# FEEL_2021_MCU.net
KiCad netlist of a schematic drawn in Altium Designer
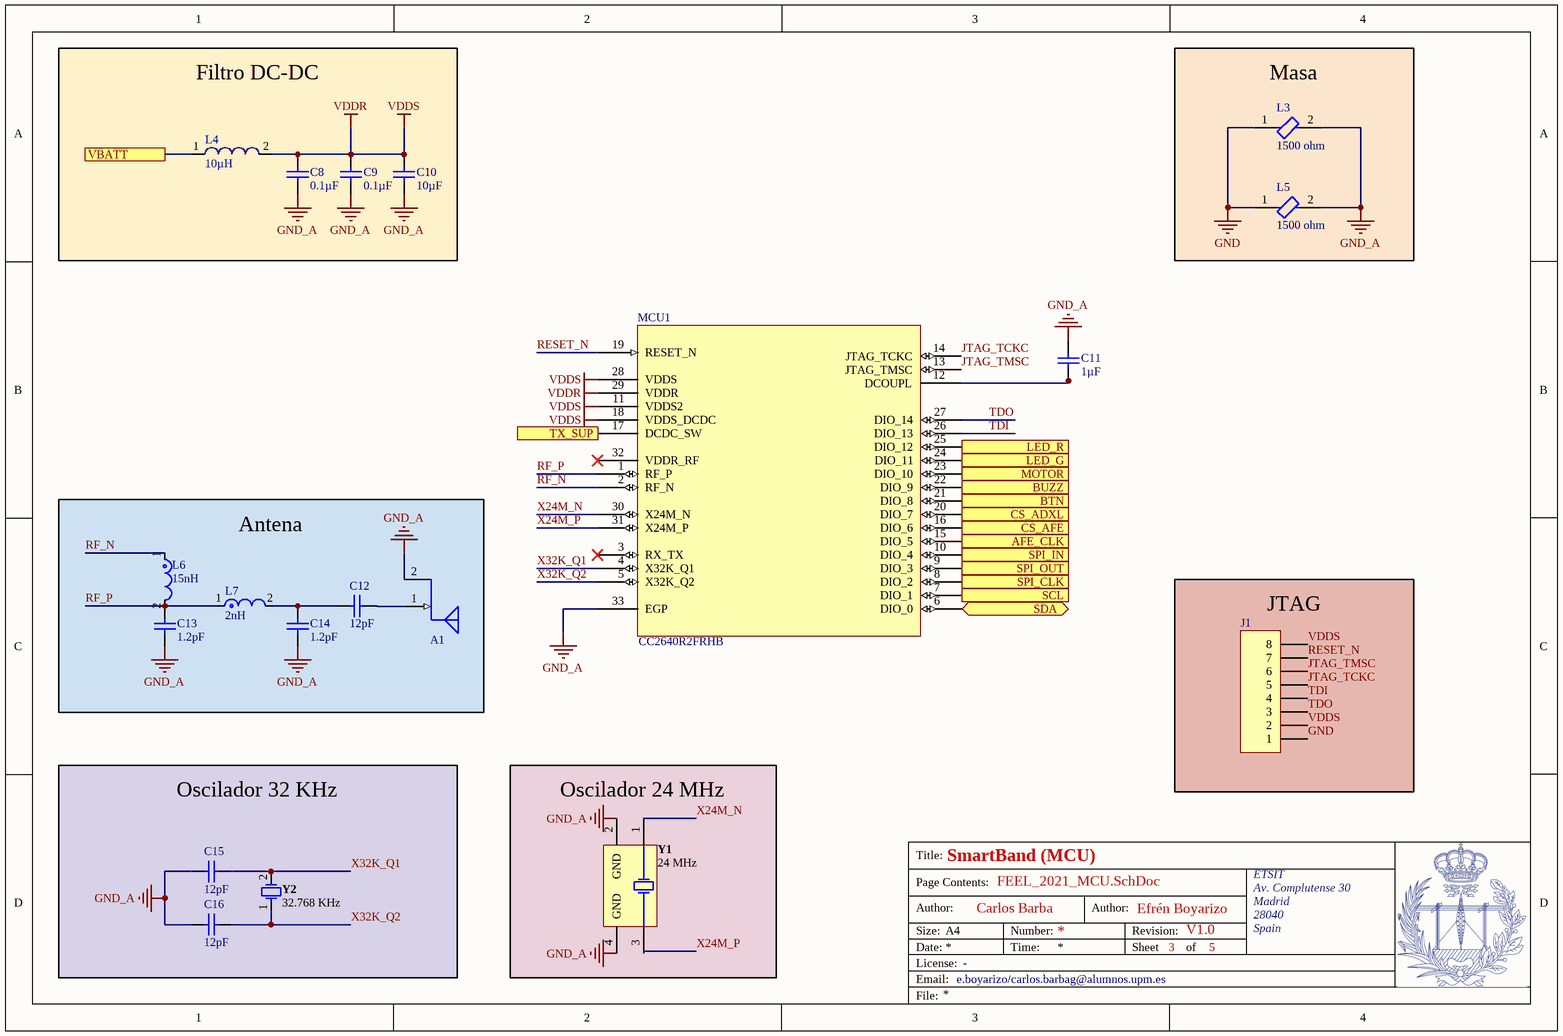
[diagram p0: FEEL_2021_MCU.SchDoc]

(export (version "E")
  (design (tool "Eeschema 10.0.6"))
  (components
    (comp (ref "A1") (value "-") (footprint "PCBAntenna") (libsource (lib "FEEL2122") (part "PCBAntenna")))
    (comp (ref "C8")
      (value "0.1µF")
      (footprint "CAPC1608X90X35ML10T15")
      (description "Chip Capacitor, 22 pF, +/- 5%, 50 V, -55 to 125 degC, 0603 (1608 Metric), RoHS, Tape and Reel")
      (fields (field (name "MANUFACTURER") "Murata"))
      (libsource (lib "Altium Content Vault") (part "CAP-NP-2"))
    )
    (comp (ref "C9")
      (value "0.1µF")
      (footprint "CAPC1608X90X35ML10T15")
      (description "Chip Capacitor, 22 pF, +/- 5%, 50 V, -55 to 125 degC, 0603 (1608 Metric), RoHS, Tape and Reel")
      (fields (field (name "MANUFACTURER") "Murata"))
      (libsource (lib "Altium Content Vault") (part "CAP-NP-2"))
    )
    (comp (ref "C10")
      (value "10µF")
      (footprint "CAPC1608X90X35ML10T15")
      (description "Chip Capacitor, 22 pF, +/- 5%, 50 V, -55 to 125 degC, 0603 (1608 Metric), RoHS, Tape and Reel")
      (fields (field (name "MANUFACTURER") "Murata"))
      (libsource (lib "Altium Content Vault") (part "CAP-NP-2"))
    )
    (comp (ref "C11")
      (value "1µF")
      (footprint "CAPC1608X90X35ML10T15")
      (description "Chip Capacitor, 22 pF, +/- 5%, 50 V, -55 to 125 degC, 0603 (1608 Metric), RoHS, Tape and Reel")
      (fields (field (name "MANUFACTURER") "Murata"))
      (libsource (lib "Altium Content Vault") (part "CAP-NP-2"))
    )
    (comp (ref "C12")
      (value "12pF")
      (footprint "CAPC1608X90X35ML10T15")
      (description "Chip Capacitor, 22 pF, +/- 5%, 50 V, -55 to 125 degC, 0603 (1608 Metric), RoHS, Tape and Reel")
      (fields (field (name "MANUFACTURER") "Murata"))
      (libsource (lib "Altium Content Vault") (part "CAP-NP-2"))
    )
    (comp (ref "C13")
      (value "1.2pF")
      (footprint "CAPC1608X90X35ML10T15")
      (description "Chip Capacitor, 22 pF, +/- 5%, 50 V, -55 to 125 degC, 0603 (1608 Metric), RoHS, Tape and Reel")
      (fields (field (name "MANUFACTURER") "Murata"))
      (libsource (lib "Altium Content Vault") (part "CAP-NP-2"))
    )
    (comp (ref "C14")
      (value "1.2pF")
      (footprint "CAPC1608X90X35ML10T15")
      (description "Chip Capacitor, 22 pF, +/- 5%, 50 V, -55 to 125 degC, 0603 (1608 Metric), RoHS, Tape and Reel")
      (fields (field (name "MANUFACTURER") "Murata"))
      (libsource (lib "Altium Content Vault") (part "CAP-NP-2"))
    )
    (comp (ref "C15")
      (value "12pF")
      (footprint "CAPC1608X90X35ML10T15")
      (description "Chip Capacitor, 22 pF, +/- 5%, 50 V, -55 to 125 degC, 0603 (1608 Metric), RoHS, Tape and Reel")
      (fields (field (name "MANUFACTURER") "Murata"))
      (libsource (lib "Altium Content Vault") (part "CAP-NP-2"))
    )
    (comp (ref "C16")
      (value "12pF")
      (footprint "CAPC1608X90X35ML10T15")
      (description "Chip Capacitor, 22 pF, +/- 5%, 50 V, -55 to 125 degC, 0603 (1608 Metric), RoHS, Tape and Reel")
      (fields (field (name "MANUFACTURER") "Murata"))
      (libsource (lib "Altium Content Vault") (part "CAP-NP-2"))
    )
    (comp (ref "J1")
      (value "~")
      (footprint "HDR1X8")
      (description "Header, 8-Pin")
      (fields (field (name "PUBLISHER") "Altium Limited"))
      (libsource (lib "Miscellaneous Connectors") (part "Header 8"))
    )
    (comp (ref "L3")
      (value "1500 ohm")
      (footprint "FP-BLM18-0_15-t0_8-MFG")
      (description "Chip Ferrite Bead, 0603, 600Ω @ 100MHz, 0.35Ω, 25%, 500mA")
      (fields (field (name "TOLERANCE") "25%"))
      (libsource (lib "Altium Content Vault") (part "5f30dd21d616792df468990f7003faa"))
    )
    (comp (ref "L4")
      (value "10µH")
      (footprint "SMD 2510")
      (description "Power Multilayer Inductor WE-MAPI, L=10.0µH")
      (fields (field (name "PARTNUMBER") "74438323100") (field (name "MANUFACTURER") "Wuerth Elektronik"))
      (libsource (lib "Altium Content Vault") (part "WE-IND-INDUCTOR-2"))
    )
    (comp (ref "L5")
      (value "1500 ohm")
      (footprint "FP-BLM18-0_15-t0_8-MFG")
      (description "Chip Ferrite Bead, 0603, 600Ω @ 100MHz, 0.35Ω, 25%, 500mA")
      (fields (field (name "TOLERANCE") "25%"))
      (libsource (lib "Altium Content Vault") (part "5f30dd21d616792df468990f7003faa"))
    )
    (comp (ref "L6")
      (value "15nH")
      (footprint "FP-LQG15HH_02-IPC_B")
      (description "Multilayer type RF Inductor 2.4nH ±0.3nH 0.1Ω 800mA 0402")
      (fields (field (name "TOLERANCE") "5%"))
      (libsource (lib "Altium Content Vault") (part "4cc4b267dca4c8e51f7102f422741d8"))
    )
    (comp (ref "L7")
      (value "2nH")
      (footprint "FP-LQG15HH_02-IPC_B")
      (description "Multilayer type RF Inductor 2.4nH ±0.3nH 0.1Ω 800mA 0402")
      (fields (field (name "TOLERANCE") "5%"))
      (libsource (lib "Altium Content Vault") (part "4cc4b267dca4c8e51f7102f422741d8"))
    )
    (comp (ref "MCU1")
      (value "~")
      (footprint "DEOP2021-Calle-Payno")
      (libsource (lib "FEEL2122") (part "CC2640R2FRHB"))
    )
    (comp (ref "Y1")
      (value "24 MHz")
      (footprint "ABRA-ABM3B-4_V")
      (description "Ceramic SMD Crystal, 24 MHz, +/- 20 ppm, 50 Ohm, -20 to 70 degC, 4-Pin SMD, RoHS, Tape and Reel")
      (libsource (lib "Altium Content Vault") (part "XTAL-1-3-4"))
    )
    (comp (ref "Y2")
      (value "32.768 KHz")
      (footprint "ABRA-ABS07_A_V")
      (description "Tuning Fork Crystal, 32.768 KHz, +/- 20 ppm, -40 to 85 degC, 2-Pin SMD, RoHS, Tape and Reel")
      (fields (field (name "MANUFACTURER") "Abracon") (field (name "TOLERANCE") "20ppm"))
      (libsource (lib "Altium Content Vault") (part "XTAL-1-2-2"))
    )
  )
  (nets
    (net (code "1") (name "/AFE_CLK") (class "Default")
      (node (ref "MCU1") (pin "15") (pinfunction "DIO_5_15") (pintype "bidirectional"))
    )
    (net (code "2") (name "/BTN") (class "Default")
      (node (ref "MCU1") (pin "21") (pinfunction "DIO_8_21") (pintype "bidirectional"))
    )
    (net (code "3") (name "/BUZZ") (class "Default")
      (node (ref "MCU1") (pin "22") (pinfunction "DIO_9_22") (pintype "bidirectional"))
    )
    (net (code "4") (name "/CS_ADXL") (class "Default")
      (node (ref "MCU1") (pin "20") (pinfunction "DIO_7_20") (pintype "bidirectional"))
    )
    (net (code "5") (name "/CS_AFE") (class "Default")
      (node (ref "MCU1") (pin "16") (pinfunction "DIO_6_16") (pintype "bidirectional"))
    )
    (net (code "6") (name "/JTAG_TCKC") (class "Default")
      (node (ref "J1") (pin "5") (pinfunction "5_5") (pintype "passive"))
      (node (ref "MCU1") (pin "14") (pinfunction "JTAG_TCKC_14") (pintype "bidirectional"))
    )
    (net (code "7") (name "/JTAG_TMSC") (class "Default")
      (node (ref "J1") (pin "6") (pinfunction "6_6") (pintype "passive"))
      (node (ref "MCU1") (pin "13") (pinfunction "JTAG_TMSC_13") (pintype "bidirectional"))
    )
    (net (code "8") (name "/LED_G") (class "Default")
      (node (ref "MCU1") (pin "24") (pinfunction "DIO_11_24") (pintype "bidirectional"))
    )
    (net (code "9") (name "/LED_R") (class "Default")
      (node (ref "MCU1") (pin "25") (pinfunction "DIO_12_25") (pintype "bidirectional"))
    )
    (net (code "10") (name "/MOTOR") (class "Default")
      (node (ref "MCU1") (pin "23") (pinfunction "DIO_10_23") (pintype "bidirectional"))
    )
    (net (code "11") (name "/RESET_N") (class "Default")
      (node (ref "J1") (pin "7") (pinfunction "7_7") (pintype "passive"))
      (node (ref "MCU1") (pin "19") (pinfunction "RESET_N_19") (pintype "input"))
    )
    (net (code "12") (name "/RF_N") (class "Default")
      (node (ref "L6") (pin "1") (pinfunction "1_1") (pintype "passive"))
      (node (ref "MCU1") (pin "2") (pinfunction "RF_N_2") (pintype "bidirectional"))
    )
    (net (code "13") (name "/RF_P") (class "Default")
      (node (ref "C13") (pin "2") (pinfunction "2_2") (pintype "passive"))
      (node (ref "L6") (pin "2") (pinfunction "2_2") (pintype "passive"))
      (node (ref "L7") (pin "1") (pinfunction "1_1") (pintype "passive"))
      (node (ref "MCU1") (pin "1") (pinfunction "RF_P_1") (pintype "bidirectional"))
    )
    (net (code "14") (name "/SCL") (class "Default")
      (node (ref "MCU1") (pin "7") (pinfunction "DIO_1_7") (pintype "bidirectional"))
    )
    (net (code "15") (name "/SDA") (class "Default")
      (node (ref "MCU1") (pin "6") (pinfunction "DIO_0_6") (pintype "bidirectional"))
    )
    (net (code "16") (name "/SPI_CLK") (class "Default")
      (node (ref "MCU1") (pin "8") (pinfunction "DIO_2_8") (pintype "bidirectional"))
    )
    (net (code "17") (name "/SPI_IN") (class "Default")
      (node (ref "MCU1") (pin "10") (pinfunction "DIO_4_10") (pintype "bidirectional"))
    )
    (net (code "18") (name "/SPI_OUT") (class "Default")
      (node (ref "MCU1") (pin "9") (pinfunction "DIO_3_9") (pintype "bidirectional"))
    )
    (net (code "19") (name "/TDI") (class "Default")
      (node (ref "J1") (pin "4") (pinfunction "4_4") (pintype "passive"))
      (node (ref "MCU1") (pin "26") (pinfunction "DIO_13_26") (pintype "bidirectional"))
    )
    (net (code "20") (name "/TDO") (class "Default")
      (node (ref "J1") (pin "3") (pinfunction "3_3") (pintype "passive"))
      (node (ref "MCU1") (pin "27") (pinfunction "DIO_14_27") (pintype "bidirectional"))
    )
    (net (code "21") (name "/TX_SUP") (class "Default")
      (node (ref "MCU1") (pin "17") (pinfunction "DCDC_SW_17") (pintype "power_in"))
    )
    (net (code "22") (name "/VBATT") (class "Default")
      (node (ref "L4") (pin "1") (pinfunction "1_1") (pintype "passive"))
    )
    (net (code "23") (name "/X24M_N") (class "Default")
      (node (ref "MCU1") (pin "30") (pinfunction "X24M_N_30") (pintype "bidirectional"))
      (node (ref "Y1") (pin "1") (pinfunction "X1_1") (pintype "passive"))
    )
    (net (code "24") (name "/X24M_P") (class "Default")
      (node (ref "MCU1") (pin "31") (pinfunction "X24M_P_31") (pintype "bidirectional"))
      (node (ref "Y1") (pin "3") (pinfunction "X2_3") (pintype "passive"))
    )
    (net (code "25") (name "/X32K_Q1") (class "Default")
      (node (ref "C15") (pin "2") (pinfunction "2_2") (pintype "passive"))
      (node (ref "MCU1") (pin "4") (pinfunction "X32K_Q1_4") (pintype "bidirectional"))
      (node (ref "Y2") (pin "2") (pinfunction "2_2") (pintype "passive"))
    )
    (net (code "26") (name "/X32K_Q2") (class "Default")
      (node (ref "C16") (pin "2") (pinfunction "2_2") (pintype "passive"))
      (node (ref "MCU1") (pin "5") (pinfunction "X32K_Q2_5") (pintype "bidirectional"))
      (node (ref "Y2") (pin "1") (pinfunction "1_1") (pintype "passive"))
    )
    (net (code "27") (name "GND") (class "Default")
      (node (ref "J1") (pin "1") (pinfunction "1_1") (pintype "passive"))
      (node (ref "L3") (pin "1") (pinfunction "1_1") (pintype "passive"))
      (node (ref "L5") (pin "1") (pinfunction "1_1") (pintype "passive"))
    )
    (net (code "28") (name "GND_A") (class "Default")
      (node (ref "A1") (pin "2") (pinfunction "GND_2") (pintype "power_in"))
      (node (ref "C10") (pin "1") (pinfunction "1_1") (pintype "passive"))
      (node (ref "C11") (pin "2") (pinfunction "2_2") (pintype "passive"))
      (node (ref "C13") (pin "1") (pinfunction "1_1") (pintype "passive"))
      (node (ref "C14") (pin "1") (pinfunction "1_1") (pintype "passive"))
      (node (ref "C15") (pin "1") (pinfunction "1_1") (pintype "passive"))
      (node (ref "C16") (pin "1") (pinfunction "1_1") (pintype "passive"))
      (node (ref "C8") (pin "1") (pinfunction "1_1") (pintype "passive"))
      (node (ref "C9") (pin "1") (pinfunction "1_1") (pintype "passive"))
      (node (ref "L3") (pin "2") (pinfunction "2_2") (pintype "passive"))
      (node (ref "L5") (pin "2") (pinfunction "2_2") (pintype "passive"))
      (node (ref "MCU1") (pin "33") (pinfunction "EGP_33") (pintype "power_in"))
      (node (ref "Y1") (pin "2") (pinfunction "GND_2") (pintype "power_in"))
      (node (ref "Y1") (pin "4") (pinfunction "GND_4") (pintype "power_in"))
    )
    (net (code "29") (name "Net-(A1-FeedPoint)") (class "Default")
      (node (ref "A1") (pin "1") (pinfunction "FeedPoint_1") (pintype "input"))
      (node (ref "C12") (pin "2") (pinfunction "2_2") (pintype "passive"))
    )
    (net (code "30") (name "Net-(C12-Pad1)") (class "Default")
      (node (ref "C12") (pin "1") (pinfunction "1_1") (pintype "passive"))
      (node (ref "C14") (pin "2") (pinfunction "2_2") (pintype "passive"))
      (node (ref "L7") (pin "2") (pinfunction "2_2") (pintype "passive"))
    )
    (net (code "31") (name "Net-(MCU1-DCOUPL)") (class "Default")
      (node (ref "C11") (pin "1") (pinfunction "1_1") (pintype "passive"))
      (node (ref "MCU1") (pin "12") (pinfunction "DCOUPL_12") (pintype "power_in"))
    )
    (net (code "32") (name "VDDR") (class "Default")
      (node (ref "C10") (pin "2") (pinfunction "2_2") (pintype "passive"))
      (node (ref "C8") (pin "2") (pinfunction "2_2") (pintype "passive"))
      (node (ref "C9") (pin "2") (pinfunction "2_2") (pintype "passive"))
      (node (ref "J1") (pin "2") (pinfunction "2_2") (pintype "passive"))
      (node (ref "J1") (pin "8") (pinfunction "8_8") (pintype "passive"))
      (node (ref "L4") (pin "2") (pinfunction "2_2") (pintype "passive"))
      (node (ref "MCU1") (pin "11") (pinfunction "VDDS2_11") (pintype "power_in"))
      (node (ref "MCU1") (pin "18") (pinfunction "VDDS_DCDC_18") (pintype "power_in"))
      (node (ref "MCU1") (pin "28") (pinfunction "VDDS_28") (pintype "power_in"))
      (node (ref "MCU1") (pin "29") (pinfunction "VDDR_29") (pintype "power_in"))
    )
    (net (code "33") (name "unconnected-(MCU1-RX_TX-Pad3)") (class "Default")
      (node (ref "MCU1") (pin "3") (pinfunction "RX_TX_3") (pintype "bidirectional+no_connect"))
    )
    (net (code "34") (name "unconnected-(MCU1-VDDR_RF-Pad32)") (class "Default")
      (node (ref "MCU1") (pin "32") (pinfunction "VDDR_RF_32") (pintype "power_in+no_connect"))
    )
  )
)
